# STM32F103T8.net
KiCad netlist of a schematic drawn in Altium Designer
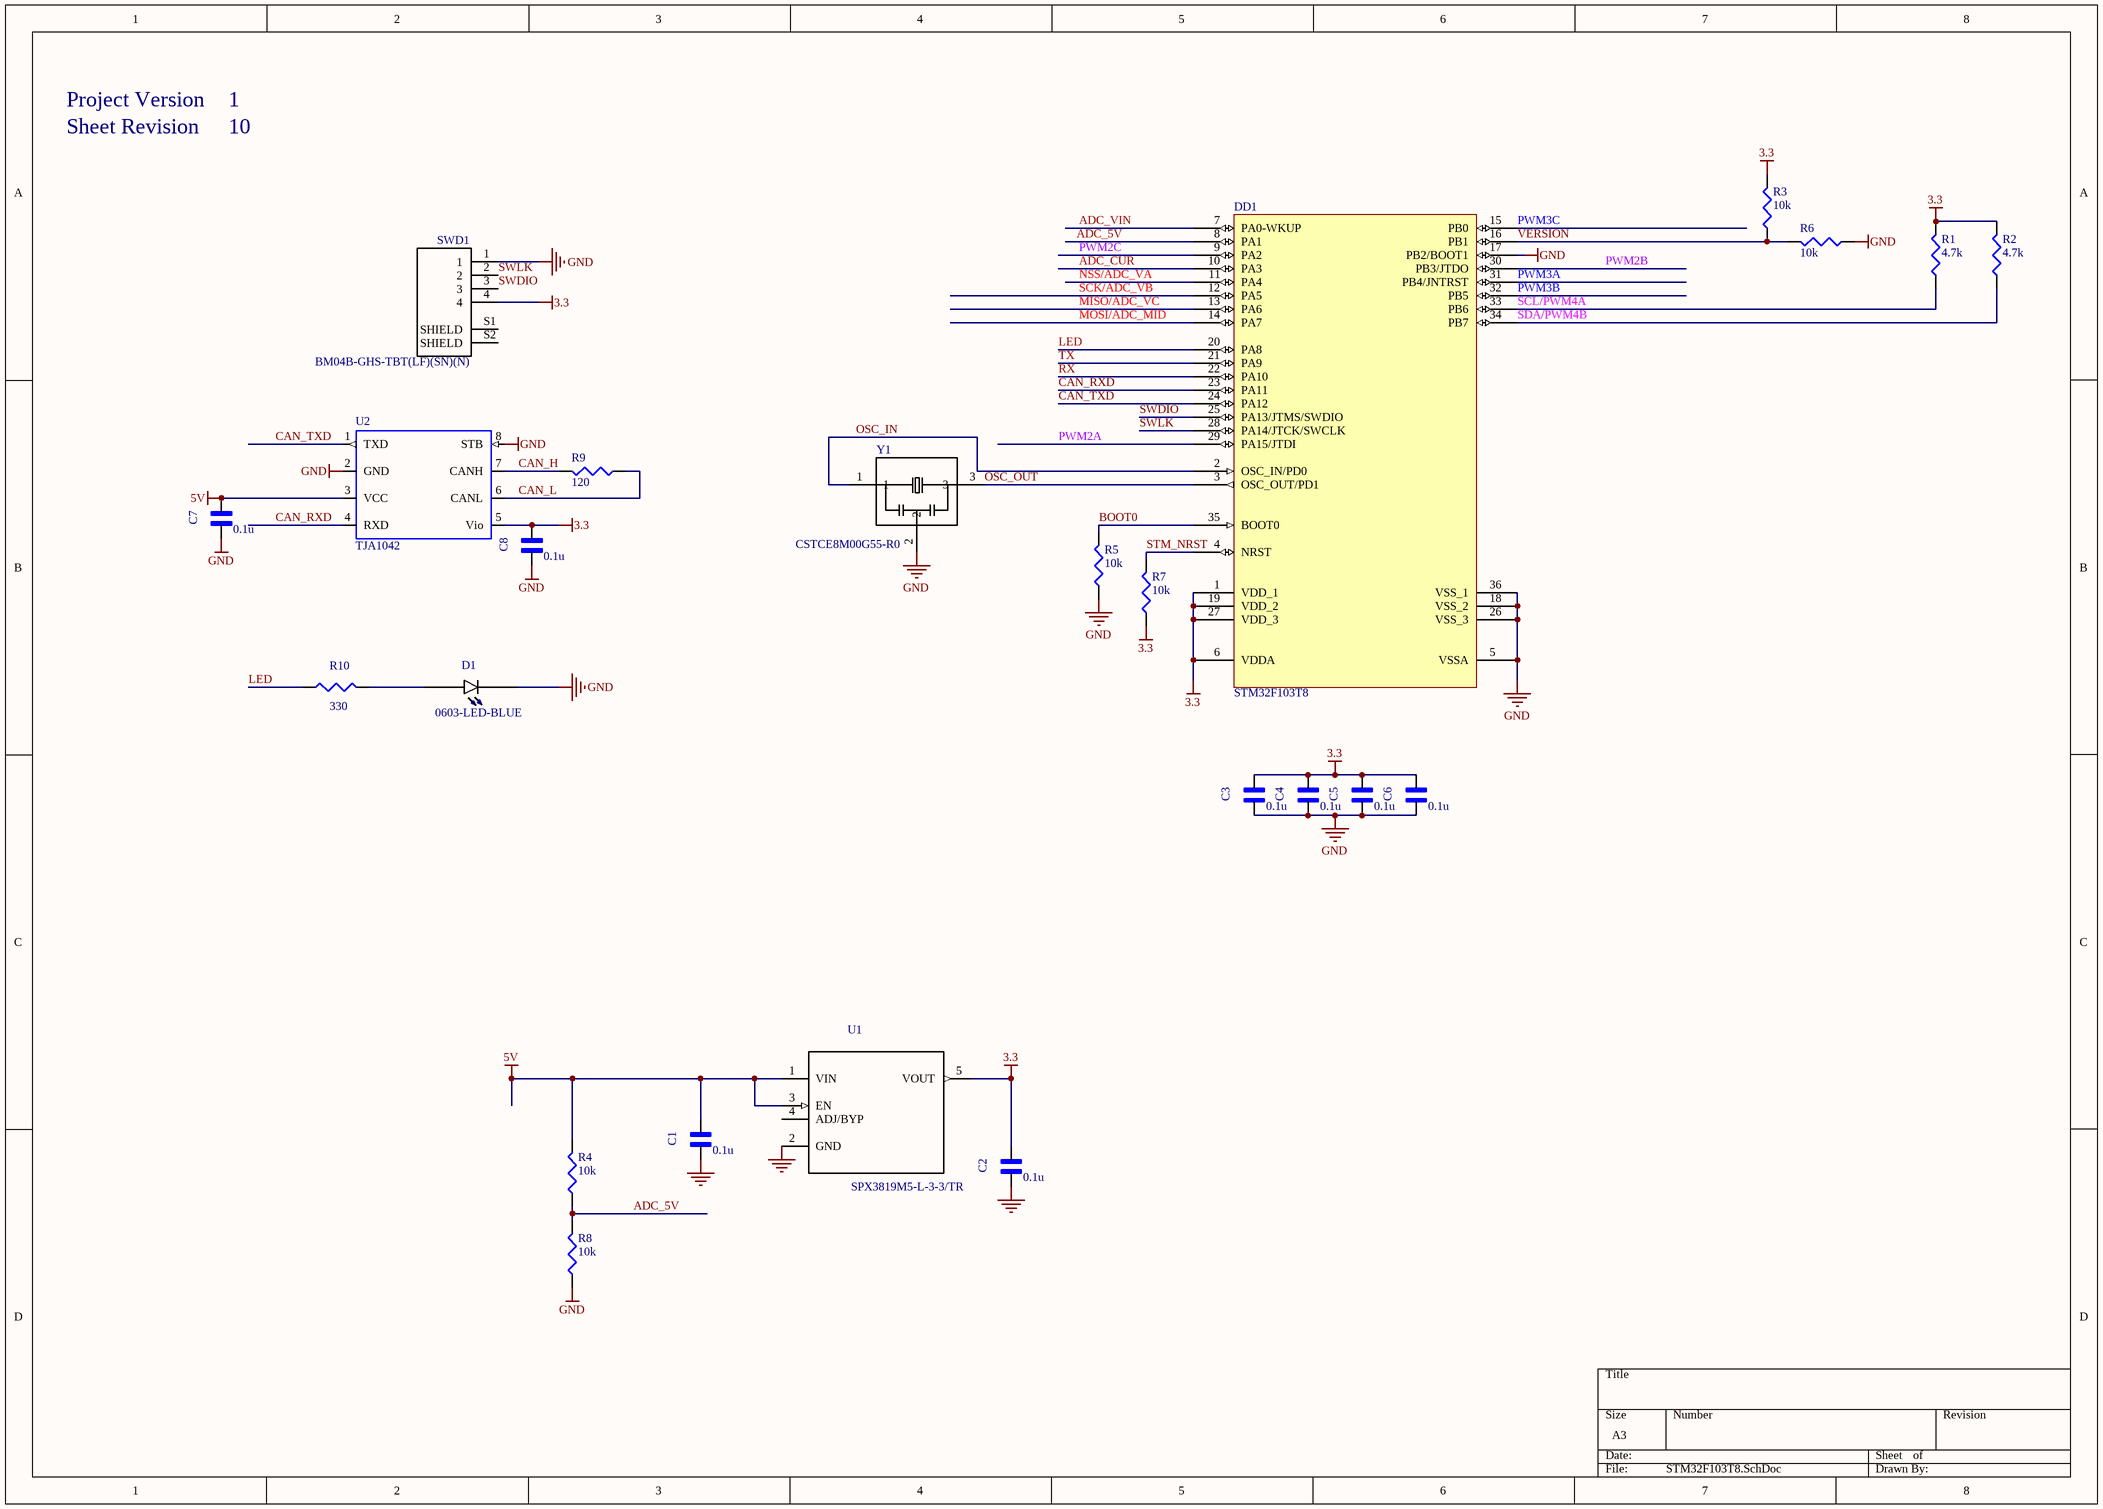
[diagram p0: STM32F103T8.SchDoc]

(export (version "E")
  (design (tool "Eeschema 10.0.6"))
  (components
    (comp (ref "C1")
      (value "0.1u")
      (footprint "*CAPC1608X90")
      (description "Cap Thin Film 0.1uf 50v 0603")
      (fields (field (name "MF") "AVX") (field (name "MP") "GX035C104MAT2-500"))
      (libsource (lib "lib") (part "GX035C104MAT2-500"))
    )
    (comp (ref "C2")
      (value "0.1u")
      (footprint "*CAPC1608X90")
      (description "Cap Thin Film 0.1uf 50v 0603")
      (fields (field (name "MF") "AVX") (field (name "MP") "GX035C104MAT2-500"))
      (libsource (lib "lib") (part "GX035C104MAT2-500"))
    )
    (comp (ref "C3")
      (value "0.1u")
      (footprint "*CAPC1608X90")
      (description "Cap Thin Film 0.1uf 50v 0603")
      (fields (field (name "MF") "AVX") (field (name "MP") "GX035C104MAT2-500 or CL10B104JB8NNNC"))
      (libsource (lib "lib") (part "GX035C104MAT2-500"))
    )
    (comp (ref "C4")
      (value "0.1u")
      (footprint "*CAPC1608X90")
      (description "Cap Thin Film 0.1uf 50v 0603")
      (fields (field (name "MF") "AVX") (field (name "MP") "GX035C104MAT2-500 or CL10B104JB8NNNC"))
      (libsource (lib "lib") (part "GX035C104MAT2-500"))
    )
    (comp (ref "C5")
      (value "0.1u")
      (footprint "*CAPC1608X90")
      (description "Cap Thin Film 0.1uf 50v 0603")
      (fields (field (name "MF") "AVX") (field (name "MP") "GX035C104MAT2-500 or CL10B104JB8NNNC"))
      (libsource (lib "lib") (part "GX035C104MAT2-500"))
    )
    (comp (ref "C6")
      (value "0.1u")
      (footprint "*CAPC1608X90")
      (description "Cap Thin Film 0.1uf 50v 0603")
      (fields (field (name "MF") "AVX") (field (name "MP") "GX035C104MAT2-500 or CL10B104JB8NNNC"))
      (libsource (lib "lib") (part "GX035C104MAT2-500"))
    )
    (comp (ref "C7")
      (value "0.1u")
      (footprint "*CAPC1608X90")
      (description "Cap Thin Film 0.1uf 50v 0603")
      (fields (field (name "MF") "AVX") (field (name "MP") "GX035C104MAT2-500 or CL10B104JB8NNNC"))
      (libsource (lib "lib") (part "GX035C104MAT2-500"))
    )
    (comp (ref "C8")
      (value "0.1u")
      (footprint "*CAPC1608X90")
      (description "Cap Thin Film 0.1uf 50v 0603")
      (fields (field (name "MF") "AVX") (field (name "MP") "GX035C104MAT2-500 or CL10B104JB8NNNC"))
      (libsource (lib "lib") (part "GX035C104MAT2-500"))
    )
    (comp (ref "D1")
      (value "0603-LED-BLUE")
      (footprint "*LEDM1608X80_LTE-C1906R-14(Primary)")
      (description "LED IrLED Chip LED 2-Pin SMD T/R")
      (libsource (lib "lib") (part "LTE-C1906R-14"))
    )
    (comp (ref "DD1")
      (value "STM32F103T8")
      (footprint "*QFN50P600X600X100-37N")
      (description "STM32F103T8U6, Микроконтроллер 32BIT ARM 64K FLASH [VFQFPN-36]")
      (fields (field (name "MF") "STM") (field (name "MP") "STM32F103T8U6"))
      (libsource (lib "lib") (part "STM32F103T8"))
    )
    (comp (ref "R1")
      (value "4.7k")
      (footprint "J1-0603")
      (description "Resistor")
      (fields (field (name "MP") "4.7K 1% 0603") (field (name "Comment") "Res3"))
      (libsource (lib "Miscellaneous Devices") (part "Res3"))
    )
    (comp (ref "R2")
      (value "4.7k")
      (footprint "J1-0603")
      (description "Resistor")
      (fields (field (name "MP") "4.7K 1% 0603") (field (name "Comment") "Res3"))
      (libsource (lib "Miscellaneous Devices") (part "Res3"))
    )
    (comp (ref "R3")
      (value "10k")
      (footprint "J1-0603")
      (description "10 kOhms 1 0.1 W 1 10 W Chip Resistor 0603 1608 Metric Thick Film")
      (fields (field (name "MF") "Yageo or NXP") (field (name "MP") "10K 1% 0603"))
      (libsource (lib "CAN_NODE_MINI") (part "RC0603FR-0710KL"))
    )
    (comp (ref "R4")
      (value "10k")
      (footprint "J1-0603")
      (description "10 kOhms 1 0.1 W 1 10 W Chip Resistor 0603 1608 Metric Thick Film")
      (fields (field (name "MF") "Yageo or NXP") (field (name "MP") "10K 1% 0603"))
      (libsource (lib "CAN_NODE_MINI") (part "RC0603FR-0710KL"))
    )
    (comp (ref "R5")
      (value "10k")
      (footprint "J1-0603")
      (description "10 kOhms 1 0.1 W 1 10 W Chip Resistor 0603 1608 Metric Thick Film")
      (fields (field (name "MF") "Yageo or NXP") (field (name "MP") "10K 1% 0603"))
      (libsource (lib "CAN_NODE_MINI") (part "RC0603FR-0710KL"))
    )
    (comp (ref "R6")
      (value "10k")
      (footprint "J1-0603")
      (description "10 kOhms 1 0.1 W 1 10 W Chip Resistor 0603 1608 Metric Thick Film")
      (fields (field (name "MF") "Yageo or NXP") (field (name "MP") "10K 1% 0603"))
      (libsource (lib "CAN_NODE_MINI") (part "RC0603FR-0710KL"))
    )
    (comp (ref "R7")
      (value "10k")
      (footprint "J1-0603")
      (description "10 kOhms 1 0.1 W 1 10 W Chip Resistor 0603 1608 Metric Thick Film")
      (fields (field (name "MF") "Yageo or NXP") (field (name "MP") "10K 1% 0603"))
      (libsource (lib "CAN_NODE_MINI") (part "RC0603FR-0710KL"))
    )
    (comp (ref "R8")
      (value "10k")
      (footprint "J1-0603")
      (description "10 kOhms 1 0.1 W 1 10 W Chip Resistor 0603 1608 Metric Thick Film")
      (fields (field (name "MF") "Yageo or NXP") (field (name "MP") "10K 1% 0603"))
      (libsource (lib "CAN_NODE_MINI") (part "RC0603FR-0710KL"))
    )
    (comp (ref "R9")
      (value "120")
      (footprint "J1-0603")
      (description "120 Ohms 1 0.1 W 1 10 W Chip Resistor 0603 1608 Metric Thick Film")
      (fields (field (name "MP") "RC0603FR-07120RL") (field (name "Comment") "Res3"))
      (libsource (lib "Miscellaneous Devices") (part "Res3"))
    )
    (comp (ref "R10")
      (value "330")
      (footprint "J1-0603")
      (description "Resistor")
      (fields (field (name "MP") "RC0603FR-07330RL") (field (name "Comment") "Res3"))
      (libsource (lib "Miscellaneous Devices") (part "Res3"))
    )
    (comp (ref "SWD1")
      (value "BM04B-GHS-TBT(LF)(SN)(N)")
      (footprint "JST_BM04B-GHS-holes")
      (description "Conn Shrouded Header HDR 4 POS 1.25mm Solder ST SMD Reel")
      (fields (field (name "MF") "JST Sales") (field (name "MP") "SM04B-GHS-TB(LF)(SN)"))
      (libsource (lib "lib") (part "BM04B-GHS-TBT(LF)(SN)(N)"))
    )
    (comp (ref "U1")
      (value "SPX3819M5-L-3-3/TR")
      (footprint "*SOT95P280X145-5N")
      (description "Low Dropout Voltage Regulator, Adjustable 0.5A, В±1%, 2.5 to 16 Vin, 5-Pin SOT-23")
      (fields (field (name "MF") "MaxLinear, Inc."))
      (libsource (lib "DC_DC") (part "SPX3819M5-L"))
    )
    (comp (ref "U2")
      (value "TJA1042")
      (footprint "SOT782-1")
      (description "1/1 Transceiver Half CANbus 8-SO")
      (fields (field (name "MF") "NXP USA"))
      (libsource (lib "lib") (part "TJA1042"))
    )
    (comp (ref "Y1")
      (value "CSTCE8M00G55-R0")
      (footprint "*OSC_CSTCE8M00G55-R0")
      (description "Ceramic Resonator 8MHz ??0.5% _Tol_ ??0.2% _Stability_ 33pF 40Ohm 3-Pin CSMD T/R")
      (fields (field (name "MF") "Murata"))
      (libsource (lib "DC_DC") (part "CSTCE8M00G55-R0"))
    )
  )
  (nets
    (net (code "1") (name "/ADC_5V") (class "Default")
      (node (ref "DD1") (pin "8") (pinfunction "PA1_8") (pintype "bidirectional"))
      (node (ref "R4") (pin "1") (pinfunction "1_1") (pintype "passive"))
      (node (ref "R8") (pin "2") (pinfunction "2_2") (pintype "passive"))
    )
    (net (code "2") (name "/ADC_CUR") (class "Default")
      (node (ref "DD1") (pin "10") (pinfunction "PA3_10") (pintype "bidirectional"))
    )
    (net (code "3") (name "/ADC_VIN") (class "Default")
      (node (ref "DD1") (pin "7") (pinfunction "PA0-WKUP_7") (pintype "bidirectional"))
    )
    (net (code "4") (name "/BOOT0") (class "Default")
      (node (ref "DD1") (pin "35") (pinfunction "BOOT0_35") (pintype "input"))
      (node (ref "R5") (pin "2") (pinfunction "2_2") (pintype "passive"))
    )
    (net (code "5") (name "/CAN_H") (class "Default")
      (node (ref "R9") (pin "2") (pinfunction "2_2") (pintype "passive"))
      (node (ref "U2") (pin "7") (pinfunction "CANH_7") (pintype "bidirectional"))
    )
    (net (code "6") (name "/CAN_L") (class "Default")
      (node (ref "R9") (pin "1") (pinfunction "1_1") (pintype "passive"))
      (node (ref "U2") (pin "6") (pinfunction "CANL_6") (pintype "bidirectional"))
    )
    (net (code "7") (name "/CAN_RXD") (class "Default")
      (node (ref "DD1") (pin "23") (pinfunction "PA11_23") (pintype "bidirectional"))
      (node (ref "U2") (pin "4") (pinfunction "RXD_4") (pintype "bidirectional"))
    )
    (net (code "8") (name "/CAN_TXD") (class "Default")
      (node (ref "DD1") (pin "24") (pinfunction "PA12_24") (pintype "bidirectional"))
      (node (ref "U2") (pin "1") (pinfunction "TXD_1") (pintype "output"))
    )
    (net (code "9") (name "/LED") (class "Default")
      (node (ref "DD1") (pin "20") (pinfunction "PA8_20") (pintype "bidirectional"))
      (node (ref "R10") (pin "1") (pinfunction "1_1") (pintype "passive"))
    )
    (net (code "10") (name "/MISO{slash}ADC_VC") (class "Default")
      (node (ref "DD1") (pin "13") (pinfunction "PA6_13") (pintype "bidirectional"))
    )
    (net (code "11") (name "/MOSI{slash}ADC_MID") (class "Default")
      (node (ref "DD1") (pin "14") (pinfunction "PA7_14") (pintype "bidirectional"))
    )
    (net (code "12") (name "/NSS{slash}ADC_VA") (class "Default")
      (node (ref "DD1") (pin "11") (pinfunction "PA4_11") (pintype "bidirectional"))
    )
    (net (code "13") (name "/OSC_IN") (class "Default")
      (node (ref "DD1") (pin "2") (pinfunction "OSC_IN/PD0_2") (pintype "input"))
      (node (ref "Y1") (pin "1") (pinfunction "1_1") (pintype "passive"))
    )
    (net (code "14") (name "/OSC_OUT") (class "Default")
      (node (ref "DD1") (pin "3") (pinfunction "OSC_OUT/PD1_3") (pintype "output"))
      (node (ref "Y1") (pin "3") (pinfunction "3_3") (pintype "passive"))
    )
    (net (code "15") (name "/PWM2A") (class "Default")
      (node (ref "DD1") (pin "29") (pinfunction "PA15/JTDI_29") (pintype "bidirectional"))
    )
    (net (code "16") (name "/PWM2B") (class "Default")
      (node (ref "DD1") (pin "30") (pinfunction "PB3/JTDO_30") (pintype "bidirectional"))
    )
    (net (code "17") (name "/PWM2C") (class "Default")
      (node (ref "DD1") (pin "9") (pinfunction "PA2_9") (pintype "bidirectional"))
    )
    (net (code "18") (name "/PWM3A") (class "Default")
      (node (ref "DD1") (pin "31") (pinfunction "PB4/JNTRST_31") (pintype "bidirectional"))
    )
    (net (code "19") (name "/PWM3B") (class "Default")
      (node (ref "DD1") (pin "32") (pinfunction "PB5_32") (pintype "bidirectional"))
    )
    (net (code "20") (name "/PWM3C") (class "Default")
      (node (ref "DD1") (pin "15") (pinfunction "PB0_15") (pintype "bidirectional"))
    )
    (net (code "21") (name "/RX") (class "Default")
      (node (ref "DD1") (pin "22") (pinfunction "PA10_22") (pintype "bidirectional"))
    )
    (net (code "22") (name "/SCK{slash}ADC_VB") (class "Default")
      (node (ref "DD1") (pin "12") (pinfunction "PA5_12") (pintype "bidirectional"))
    )
    (net (code "23") (name "/SCL{slash}PWM4A") (class "Default")
      (node (ref "DD1") (pin "33") (pinfunction "PB6_33") (pintype "bidirectional"))
      (node (ref "R1") (pin "1") (pinfunction "1_1") (pintype "passive"))
    )
    (net (code "24") (name "/SDA{slash}PWM4B") (class "Default")
      (node (ref "DD1") (pin "34") (pinfunction "PB7_34") (pintype "bidirectional"))
      (node (ref "R2") (pin "1") (pinfunction "1_1") (pintype "passive"))
    )
    (net (code "25") (name "/STM_NRST") (class "Default")
      (node (ref "DD1") (pin "4") (pinfunction "NRST_4") (pintype "bidirectional"))
      (node (ref "R7") (pin "2") (pinfunction "2_2") (pintype "passive"))
    )
    (net (code "26") (name "/SWDIO") (class "Default")
      (node (ref "DD1") (pin "25") (pinfunction "PA13/JTMS/SWDIO_25") (pintype "bidirectional"))
      (node (ref "SWD1") (pin "3") (pinfunction "3_3") (pintype "passive"))
    )
    (net (code "27") (name "/SWLK") (class "Default")
      (node (ref "DD1") (pin "28") (pinfunction "PA14/JTCK/SWCLK_28") (pintype "bidirectional"))
      (node (ref "SWD1") (pin "2") (pinfunction "2_2") (pintype "passive"))
    )
    (net (code "28") (name "/TX") (class "Default")
      (node (ref "DD1") (pin "21") (pinfunction "PA9_21") (pintype "bidirectional"))
    )
    (net (code "29") (name "/VERSION") (class "Default")
      (node (ref "DD1") (pin "16") (pinfunction "PB1_16") (pintype "bidirectional"))
      (node (ref "R3") (pin "1") (pinfunction "1_1") (pintype "passive"))
      (node (ref "R6") (pin "2") (pinfunction "2_2") (pintype "passive"))
    )
    (net (code "30") (name "3.3") (class "Default")
      (node (ref "C2") (pin "1") (pinfunction "1_1") (pintype "passive"))
      (node (ref "C3") (pin "1") (pinfunction "1_1") (pintype "passive"))
      (node (ref "C4") (pin "1") (pinfunction "1_1") (pintype "passive"))
      (node (ref "C5") (pin "1") (pinfunction "1_1") (pintype "passive"))
      (node (ref "C6") (pin "1") (pinfunction "1_1") (pintype "passive"))
      (node (ref "C8") (pin "1") (pinfunction "1_1") (pintype "passive"))
      (node (ref "DD1") (pin "1") (pinfunction "VDD_1_1") (pintype "power_in"))
      (node (ref "DD1") (pin "19") (pinfunction "VDD_2_19") (pintype "power_in"))
      (node (ref "DD1") (pin "27") (pinfunction "VDD_3_27") (pintype "power_in"))
      (node (ref "DD1") (pin "6") (pinfunction "VDDA_6") (pintype "power_in"))
      (node (ref "R1") (pin "2") (pinfunction "2_2") (pintype "passive"))
      (node (ref "R2") (pin "2") (pinfunction "2_2") (pintype "passive"))
      (node (ref "R3") (pin "2") (pinfunction "2_2") (pintype "passive"))
      (node (ref "R7") (pin "1") (pinfunction "1_1") (pintype "passive"))
      (node (ref "SWD1") (pin "4") (pinfunction "4_4") (pintype "passive"))
      (node (ref "U1") (pin "5") (pinfunction "VOUT_5") (pintype "output"))
      (node (ref "U2") (pin "5") (pinfunction "Vio_5") (pintype "power_in"))
    )
    (net (code "31") (name "5V") (class "Default")
      (node (ref "C1") (pin "1") (pinfunction "1_1") (pintype "passive"))
      (node (ref "C7") (pin "1") (pinfunction "1_1") (pintype "passive"))
      (node (ref "R4") (pin "2") (pinfunction "2_2") (pintype "passive"))
      (node (ref "U1") (pin "1") (pinfunction "VIN_1") (pintype "power_in"))
      (node (ref "U1") (pin "3") (pinfunction "EN_3") (pintype "input"))
      (node (ref "U2") (pin "3") (pinfunction "VCC_3") (pintype "power_in"))
    )
    (net (code "32") (name "GND") (class "Default")
      (node (ref "C1") (pin "2") (pinfunction "2_2") (pintype "passive"))
      (node (ref "C2") (pin "2") (pinfunction "2_2") (pintype "passive"))
      (node (ref "C3") (pin "2") (pinfunction "2_2") (pintype "passive"))
      (node (ref "C4") (pin "2") (pinfunction "2_2") (pintype "passive"))
      (node (ref "C5") (pin "2") (pinfunction "2_2") (pintype "passive"))
      (node (ref "C6") (pin "2") (pinfunction "2_2") (pintype "passive"))
      (node (ref "C7") (pin "2") (pinfunction "2_2") (pintype "passive"))
      (node (ref "C8") (pin "2") (pinfunction "2_2") (pintype "passive"))
      (node (ref "D1") (pin "C") (pinfunction "C_C") (pintype "passive"))
      (node (ref "DD1") (pin "17") (pinfunction "PB2/BOOT1_17") (pintype "bidirectional"))
      (node (ref "DD1") (pin "18") (pinfunction "VSS_2_18") (pintype "power_in"))
      (node (ref "DD1") (pin "26") (pinfunction "VSS_3_26") (pintype "power_in"))
      (node (ref "DD1") (pin "36") (pinfunction "VSS_1_36") (pintype "power_in"))
      (node (ref "DD1") (pin "5") (pinfunction "VSSA_5") (pintype "power_in"))
      (node (ref "R5") (pin "1") (pinfunction "1_1") (pintype "passive"))
      (node (ref "R6") (pin "1") (pinfunction "1_1") (pintype "passive"))
      (node (ref "R8") (pin "1") (pinfunction "1_1") (pintype "passive"))
      (node (ref "SWD1") (pin "1") (pinfunction "1_1") (pintype "passive"))
      (node (ref "U1") (pin "2") (pinfunction "GND_2") (pintype "passive"))
      (node (ref "U2") (pin "2") (pinfunction "GND_2") (pintype "power_in"))
      (node (ref "U2") (pin "8") (pinfunction "STB_8") (pintype "input"))
      (node (ref "Y1") (pin "2") (pinfunction "2_2") (pintype "power_in"))
    )
    (net (code "33") (name "Net-(D1-PadA)") (class "Default")
      (node (ref "D1") (pin "A") (pinfunction "A_A") (pintype "passive"))
      (node (ref "R10") (pin "2") (pinfunction "2_2") (pintype "passive"))
    )
    (net (code "34") (name "unconnected-(SWD1-SHIELD-PadS1)") (class "Default")
      (node (ref "SWD1") (pin "S1") (pinfunction "SHIELD_S1") (pintype "passive"))
    )
    (net (code "35") (name "unconnected-(SWD1-SHIELD-PadS2)") (class "Default")
      (node (ref "SWD1") (pin "S2") (pinfunction "SHIELD_S2") (pintype "passive"))
    )
    (net (code "36") (name "unconnected-(U1-ADJ{slash}BYP-Pad4)") (class "Default")
      (node (ref "U1") (pin "4") (pinfunction "ADJ/BYP_4") (pintype "passive"))
    )
  )
)
